# DOORLOCK.net
KiCad netlist of a schematic drawn in EAGLE
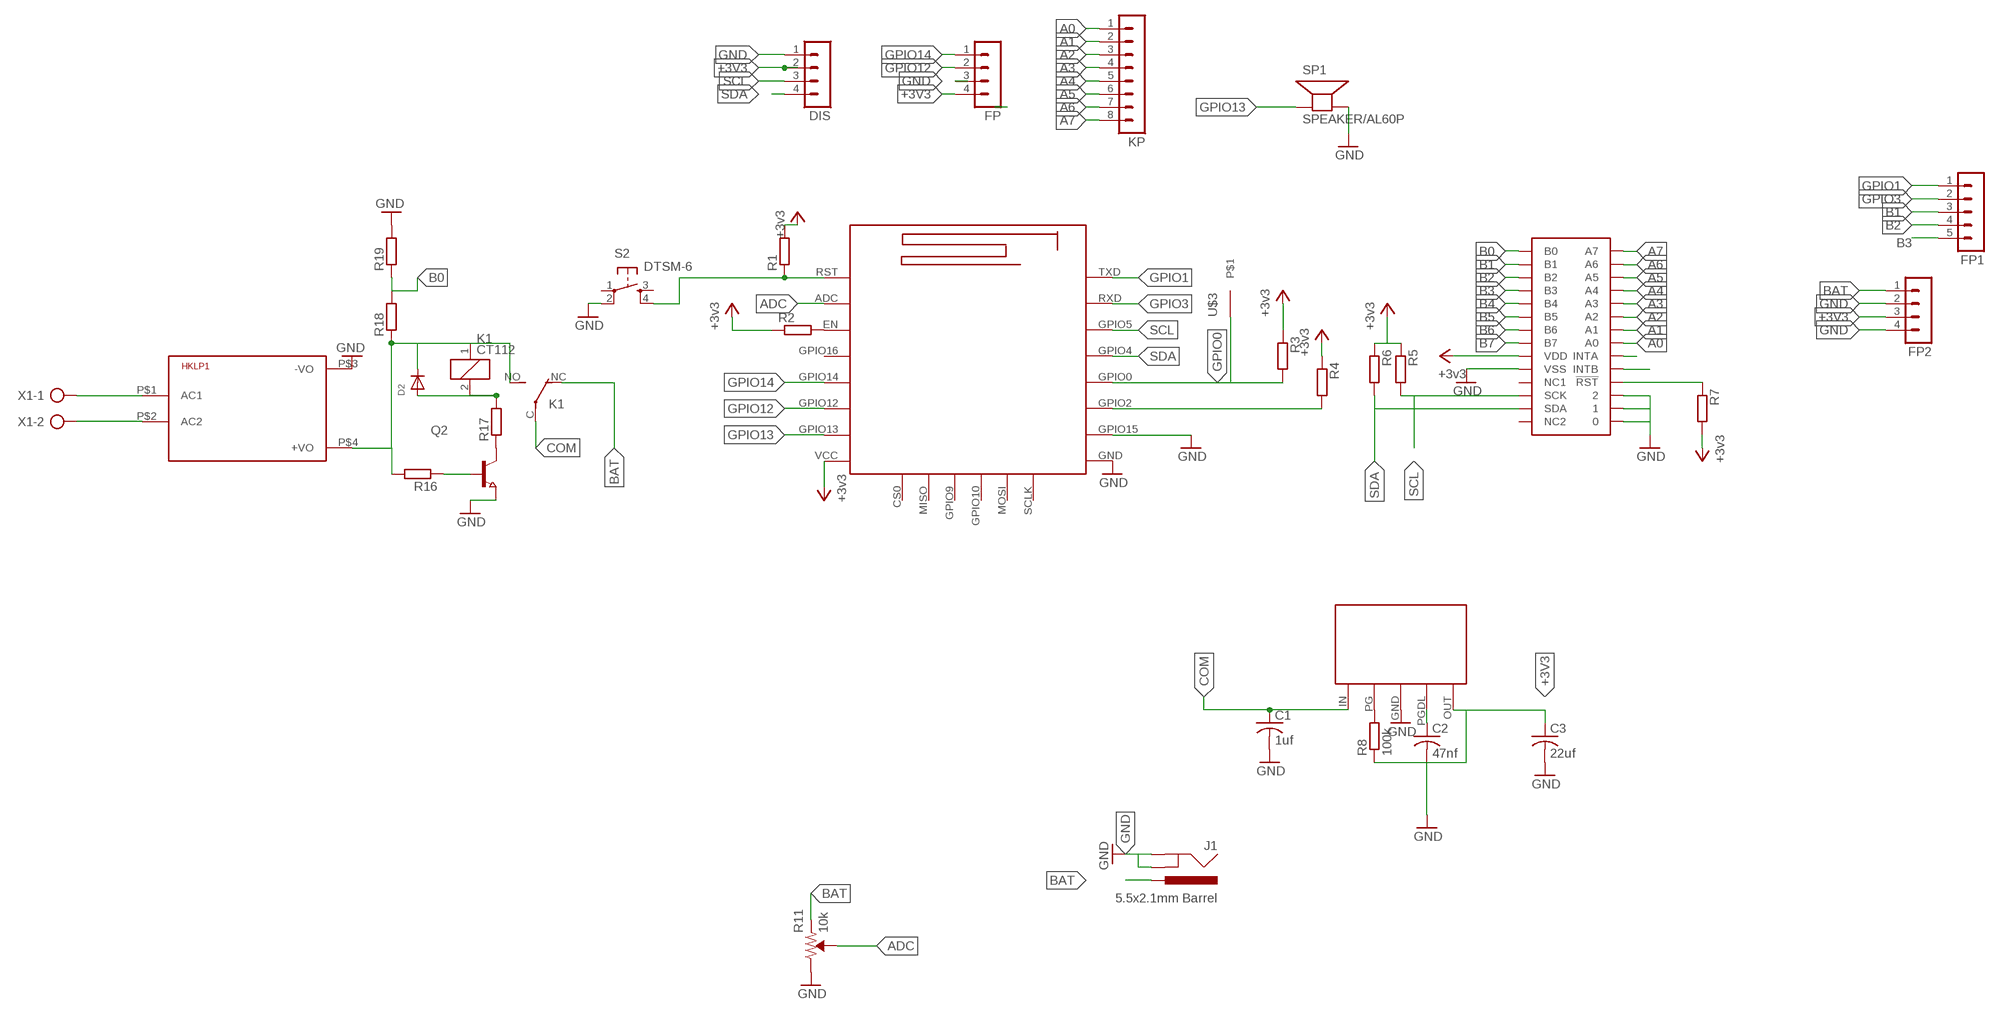
[diagram p0: schematic, sheet 1]

(export (version "E")
  (design (tool "Eeschema 10.0.6"))
  (components
    (comp (ref "C1")
      (value "1uf")
      (footprint "eagle-import:C1206")
      (libsource (lib "eagle-import") (part "C-USC1206"))
    )
    (comp (ref "C2")
      (value "47nf")
      (footprint "eagle-import:C1206")
      (libsource (lib "eagle-import") (part "C-USC1206"))
    )
    (comp (ref "C3")
      (value "22uf")
      (footprint "eagle-import:C1206")
      (libsource (lib "eagle-import") (part "C-USC1206"))
    )
    (comp (ref "D2")
      (value "DIODESOD-123")
      (footprint "eagle-import:SOD-123")
      (libsource (lib "eagle-import") (part "DIODESOD-123"))
    )
    (comp (ref "DIS")
      (value "MA04-1")
      (footprint "eagle-import:MA04-1")
      (libsource (lib "eagle-import") (part "MA04-1"))
    )
    (comp (ref "FP")
      (value "MA04-1")
      (footprint "eagle-import:MA04-1")
      (libsource (lib "eagle-import") (part "MA04-1"))
    )
    (comp (ref "FP1")
      (value "MA05-1")
      (footprint "eagle-import:MA05-1")
      (libsource (lib "eagle-import") (part "MA05-1"))
    )
    (comp (ref "FP2")
      (value "MA04-1")
      (footprint "eagle-import:MA04-1")
      (libsource (lib "eagle-import") (part "MA04-1"))
    )
    (comp (ref "HKLP1")
      (value "HKLPM01")
      (footprint "eagle-import:HKLPM01")
      (libsource (lib "eagle-import") (part "HKLPM01"))
    )
    (comp (ref "J1")
      (value "5.5x2.1mm Barrel")
      (footprint "eagle-import:POWER_JACK_SMD")
      (libsource (lib "eagle-import") (part "POWER_JACKSMD"))
    )
    (comp (ref "K1")
      (value "CT112")
      (footprint "eagle-import:CT-SLIM")
      (libsource (lib "eagle-import") (part "CT112"))
    )
    (comp (ref "KP")
      (value "MA08-1")
      (footprint "eagle-import:MA08-1")
      (libsource (lib "eagle-import") (part "MA08-1"))
    )
    (comp (ref "Q2")
      (value "NPN-TRANSISTOR_SOT89")
      (footprint "eagle-import:SOT89")
      (libsource (lib "eagle-import") (part "NPN-TRANSISTOR_SOT89"))
    )
    (comp (ref "R1")
      (value "R-EU_0204/2V")
      (footprint "eagle-import:0204V")
      (libsource (lib "eagle-import") (part "R-EU_0204/2V"))
    )
    (comp (ref "R2")
      (value "R-EU_0204/2V")
      (footprint "eagle-import:0204V")
      (libsource (lib "eagle-import") (part "R-EU_0204/2V"))
    )
    (comp (ref "R3")
      (value "R-EU_0204/2V")
      (footprint "eagle-import:0204V")
      (libsource (lib "eagle-import") (part "R-EU_0204/2V"))
    )
    (comp (ref "R4")
      (value "R-EU_0204/2V")
      (footprint "eagle-import:0204V")
      (libsource (lib "eagle-import") (part "R-EU_0204/2V"))
    )
    (comp (ref "R5")
      (value "R-EU_0204/2V")
      (footprint "eagle-import:0204V")
      (libsource (lib "eagle-import") (part "R-EU_0204/2V"))
    )
    (comp (ref "R6")
      (value "R-EU_0204/2V")
      (footprint "eagle-import:0204V")
      (libsource (lib "eagle-import") (part "R-EU_0204/2V"))
    )
    (comp (ref "R7")
      (value "R-EU_0204/2V")
      (footprint "eagle-import:0204V")
      (libsource (lib "eagle-import") (part "R-EU_0204/2V"))
    )
    (comp (ref "R8")
      (value "100k")
      (footprint "eagle-import:0204V")
      (libsource (lib "eagle-import") (part "R-EU_0204/2V"))
    )
    (comp (ref "R11")
      (value "10k")
      (footprint "eagle-import:TRIMPOT-SMD-TC33X")
      (libsource (lib "eagle-import") (part "TRIMPOT-SMD-3MM-OPEN-1/10W-25%"))
    )
    (comp (ref "R16")
      (value "R-EU_0204/2V")
      (footprint "eagle-import:0204V")
      (libsource (lib "eagle-import") (part "R-EU_0204/2V"))
    )
    (comp (ref "R17")
      (value "R-EU_0204/2V")
      (footprint "eagle-import:0204V")
      (libsource (lib "eagle-import") (part "R-EU_0204/2V"))
    )
    (comp (ref "R18")
      (value "R-EU_0204/2V")
      (footprint "eagle-import:0204V")
      (libsource (lib "eagle-import") (part "R-EU_0204/2V"))
    )
    (comp (ref "R19")
      (value "R-EU_0204/2V")
      (footprint "eagle-import:0204V")
      (libsource (lib "eagle-import") (part "R-EU_0204/2V"))
    )
    (comp (ref "S2")
      (value "DTSM-6")
      (footprint "eagle-import:DTSM-6")
      (libsource (lib "eagle-import") (part "DTSM-6"))
    )
    (comp (ref "SP1")
      (value "SPEAKER/AL60P")
      (footprint "eagle-import:AL60P")
      (libsource (lib "eagle-import") (part "SPEAKER/AL60P"))
    )
    (comp (ref "U$1")
      (value "ESP12E")
      (footprint "eagle-import:ESP-12E")
      (libsource (lib "eagle-import") (part "ESP12E"))
    )
    (comp (ref "U$2")
      (value "MCF23017")
      (footprint "eagle-import:MAX23017")
      (libsource (lib "eagle-import") (part "MCF23017"))
    )
    (comp (ref "U$3") (value "M1") (footprint "eagle-import:M1") (libsource (lib "eagle-import") (part "M1")))
    (comp (ref "U$4")
      (value "MP2014")
      (footprint "eagle-import:MP2014")
      (libsource (lib "eagle-import") (part "MP2014"))
    )
    (comp (ref "X1")
      (value "AK500/2-H")
      (footprint "eagle-import:AK500_2-H")
      (libsource (lib "eagle-import") (part "AK500/2-H"))
    )
  )
  (nets
    (net (code "1") (name "+3V3") (class "Default")
      (node (ref "C3") (pin "1") (pinfunction "1_1") (pintype "passive"))
      (node (ref "DIS") (pin "2") (pinfunction "2_2") (pintype "passive"))
      (node (ref "FP") (pin "4") (pinfunction "4_4") (pintype "passive"))
      (node (ref "FP2") (pin "3") (pinfunction "3_3") (pintype "passive"))
      (node (ref "R1") (pin "2") (pinfunction "2_2") (pintype "passive"))
      (node (ref "R2") (pin "1") (pinfunction "1_1") (pintype "passive"))
      (node (ref "R3") (pin "1") (pinfunction "1_1") (pintype "passive"))
      (node (ref "R4") (pin "1") (pinfunction "1_1") (pintype "passive"))
      (node (ref "R5") (pin "1") (pinfunction "1_1") (pintype "passive"))
      (node (ref "R6") (pin "1") (pinfunction "1_1") (pintype "passive"))
      (node (ref "R7") (pin "2") (pinfunction "2_2") (pintype "passive"))
      (node (ref "R8") (pin "1") (pinfunction "1_1") (pintype "passive"))
      (node (ref "U$1") (pin "VCC") (pinfunction "P$8_VCC") (pintype "bidirectional"))
      (node (ref "U$2") (pin "P$9") (pinfunction "VDD_P$9") (pintype "bidirectional"))
      (node (ref "U$4") (pin "OUT") (pinfunction "P$5_OUT") (pintype "bidirectional"))
    )
    (net (code "2") (name "A0") (class "Default")
      (node (ref "KP") (pin "1") (pinfunction "1_1") (pintype "passive"))
      (node (ref "U$2") (pin "P$21") (pinfunction "A0_P$21") (pintype "bidirectional"))
    )
    (net (code "3") (name "A1") (class "Default")
      (node (ref "KP") (pin "2") (pinfunction "2_2") (pintype "passive"))
      (node (ref "U$2") (pin "P$22") (pinfunction "A1_P$22") (pintype "bidirectional"))
    )
    (net (code "4") (name "A2") (class "Default")
      (node (ref "KP") (pin "3") (pinfunction "3_3") (pintype "passive"))
      (node (ref "U$2") (pin "P$23") (pinfunction "A2_P$23") (pintype "bidirectional"))
    )
    (net (code "5") (name "A3") (class "Default")
      (node (ref "KP") (pin "4") (pinfunction "4_4") (pintype "passive"))
      (node (ref "U$2") (pin "P$24") (pinfunction "A3_P$24") (pintype "bidirectional"))
    )
    (net (code "6") (name "A4") (class "Default")
      (node (ref "KP") (pin "5") (pinfunction "5_5") (pintype "passive"))
      (node (ref "U$2") (pin "P$25") (pinfunction "A4_P$25") (pintype "bidirectional"))
    )
    (net (code "7") (name "A5") (class "Default")
      (node (ref "KP") (pin "6") (pinfunction "6_6") (pintype "passive"))
      (node (ref "U$2") (pin "P$26") (pinfunction "A5_P$26") (pintype "bidirectional"))
    )
    (net (code "8") (name "A6") (class "Default")
      (node (ref "KP") (pin "7") (pinfunction "7_7") (pintype "passive"))
      (node (ref "U$2") (pin "P$27") (pinfunction "A6_P$27") (pintype "bidirectional"))
    )
    (net (code "9") (name "A7") (class "Default")
      (node (ref "KP") (pin "8") (pinfunction "8_8") (pintype "passive"))
      (node (ref "U$2") (pin "P$28") (pinfunction "A7_P$28") (pintype "bidirectional"))
    )
    (net (code "10") (name "ADC") (class "Default")
      (node (ref "R11") (pin "2") (pinfunction "WIPER_2") (pintype "passive"))
      (node (ref "U$1") (pin "ADC") (pinfunction "P$2_ADC") (pintype "bidirectional"))
    )
    (net (code "11") (name "B0") (class "Default")
      (node (ref "R18") (pin "2") (pinfunction "2_2") (pintype "passive"))
      (node (ref "R19") (pin "1") (pinfunction "1_1") (pintype "passive"))
      (node (ref "U$2") (pin "P$1") (pinfunction "B0_P$1") (pintype "bidirectional"))
    )
    (net (code "12") (name "B1") (class "Default")
      (node (ref "FP1") (pin "3") (pinfunction "3_3") (pintype "passive"))
      (node (ref "U$2") (pin "P$2") (pinfunction "B1_P$2") (pintype "bidirectional"))
    )
    (net (code "13") (name "B2") (class "Default")
      (node (ref "FP1") (pin "4") (pinfunction "4_4") (pintype "passive"))
      (node (ref "U$2") (pin "P$3") (pinfunction "B2_P$3") (pintype "bidirectional"))
    )
    (net (code "14") (name "B3") (class "Default")
      (node (ref "FP1") (pin "5") (pinfunction "5_5") (pintype "passive"))
      (node (ref "U$2") (pin "P$4") (pinfunction "B3_P$4") (pintype "bidirectional"))
    )
    (net (code "15") (name "B4") (class "Default")
      (node (ref "U$2") (pin "P$5") (pinfunction "B4_P$5") (pintype "bidirectional"))
    )
    (net (code "16") (name "B5") (class "Default")
      (node (ref "U$2") (pin "P$6") (pinfunction "B5_P$6") (pintype "bidirectional"))
    )
    (net (code "17") (name "B6") (class "Default")
      (node (ref "U$2") (pin "P$7") (pinfunction "B6_P$7") (pintype "bidirectional"))
    )
    (net (code "18") (name "B7") (class "Default")
      (node (ref "U$2") (pin "P$8") (pinfunction "B7_P$8") (pintype "bidirectional"))
    )
    (net (code "19") (name "BAT") (class "Default")
      (node (ref "FP2") (pin "1") (pinfunction "1_1") (pintype "passive"))
      (node (ref "J1") (pin "VIN0") (pinfunction "PWR_VIN0") (pintype "bidirectional"))
      (node (ref "K1") (pin "NC") (pinfunction "O_NC") (pintype "passive"))
      (node (ref "R11") (pin "3") (pinfunction "CCW_3") (pintype "passive"))
    )
    (net (code "20") (name "COM") (class "Default")
      (node (ref "C1") (pin "1") (pinfunction "1_1") (pintype "passive"))
      (node (ref "K1") (pin "C") (pinfunction "P_C") (pintype "passive"))
      (node (ref "U$4") (pin "IN") (pinfunction "P$1_IN") (pintype "bidirectional"))
    )
    (net (code "21") (name "GND") (class "Default")
      (node (ref "C1") (pin "2") (pinfunction "2_2") (pintype "passive"))
      (node (ref "C2") (pin "2") (pinfunction "2_2") (pintype "passive"))
      (node (ref "C3") (pin "2") (pinfunction "2_2") (pintype "passive"))
      (node (ref "DIS") (pin "1") (pinfunction "1_1") (pintype "passive"))
      (node (ref "FP") (pin "3") (pinfunction "3_3") (pintype "passive"))
      (node (ref "FP2") (pin "2") (pinfunction "2_2") (pintype "passive"))
      (node (ref "FP2") (pin "4") (pinfunction "4_4") (pintype "passive"))
      (node (ref "HKLP1") (pin "P$3") (pinfunction "-VO_P$3") (pintype "bidirectional"))
      (node (ref "J1") (pin "GND") (pinfunction "GNDBREAK_GND") (pintype "bidirectional"))
      (node (ref "J1") (pin "P$4") (pinfunction "GND_P$4") (pintype "bidirectional"))
      (node (ref "Q2") (pin "3") (pinfunction "E_3") (pintype "passive"))
      (node (ref "R11") (pin "1") (pinfunction "CW_1") (pintype "passive"))
      (node (ref "R19") (pin "2") (pinfunction "2_2") (pintype "passive"))
      (node (ref "S2") (pin "2") (pinfunction "2_2") (pintype "passive"))
      (node (ref "SP1") (pin "2") (pinfunction "-_2") (pintype "passive"))
      (node (ref "U$1") (pin "GND") (pinfunction "P$15_GND") (pintype "bidirectional"))
      (node (ref "U$1") (pin "GPIO15") (pinfunction "P$16_GPIO15") (pintype "bidirectional"))
      (node (ref "U$2") (pin "P$10") (pinfunction "VSS_P$10") (pintype "bidirectional"))
      (node (ref "U$2") (pin "P$15") (pinfunction "0_P$15") (pintype "bidirectional"))
      (node (ref "U$2") (pin "P$16") (pinfunction "1_P$16") (pintype "bidirectional"))
      (node (ref "U$2") (pin "P$17") (pinfunction "2_P$17") (pintype "bidirectional"))
      (node (ref "U$4") (pin "GND") (pinfunction "P$3_GND") (pintype "bidirectional"))
    )
    (net (code "22") (name "GPIO0") (class "Default")
      (node (ref "R3") (pin "2") (pinfunction "2_2") (pintype "passive"))
      (node (ref "U$1") (pin "GPIO0") (pinfunction "P$18_GPIO0") (pintype "bidirectional"))
      (node (ref "U$3") (pin "P$1") (pinfunction "P$1_P$1") (pintype "bidirectional"))
    )
    (net (code "23") (name "GPIO1") (class "Default")
      (node (ref "FP1") (pin "1") (pinfunction "1_1") (pintype "passive"))
      (node (ref "U$1") (pin "TXD") (pinfunction "P$22_TXD") (pintype "bidirectional"))
    )
    (net (code "24") (name "GPIO3") (class "Default")
      (node (ref "FP1") (pin "2") (pinfunction "2_2") (pintype "passive"))
      (node (ref "U$1") (pin "RXD") (pinfunction "P$21_RXD") (pintype "bidirectional"))
    )
    (net (code "25") (name "GPIO12") (class "Default")
      (node (ref "FP") (pin "2") (pinfunction "2_2") (pintype "passive"))
      (node (ref "U$1") (pin "GPIO12") (pinfunction "P$6_GPIO12") (pintype "bidirectional"))
    )
    (net (code "26") (name "GPIO13") (class "Default")
      (node (ref "SP1") (pin "1") (pinfunction "+_1") (pintype "passive"))
      (node (ref "U$1") (pin "GPIO13") (pinfunction "P$7_GPIO13") (pintype "bidirectional"))
    )
    (net (code "27") (name "GPIO14") (class "Default")
      (node (ref "FP") (pin "1") (pinfunction "1_1") (pintype "passive"))
      (node (ref "U$1") (pin "GPIO14") (pinfunction "P$5_GPIO14") (pintype "bidirectional"))
    )
    (net (code "28") (name "Net-(D2-PadA)") (class "Default")
      (node (ref "D2") (pin "A") (pinfunction "A_A") (pintype "passive"))
      (node (ref "K1") (pin "2") (pinfunction "2_2") (pintype "passive"))
      (node (ref "R17") (pin "2") (pinfunction "2_2") (pintype "passive"))
    )
    (net (code "29") (name "Net-(HKLP1-+VO)") (class "Default")
      (node (ref "D2") (pin "C") (pinfunction "C_C") (pintype "passive"))
      (node (ref "HKLP1") (pin "P$4") (pinfunction "+VO_P$4") (pintype "bidirectional"))
      (node (ref "K1") (pin "1") (pinfunction "1_1") (pintype "passive"))
      (node (ref "K1") (pin "NO") (pinfunction "S_NO") (pintype "passive"))
      (node (ref "R16") (pin "2") (pinfunction "2_2") (pintype "passive"))
      (node (ref "R18") (pin "1") (pinfunction "1_1") (pintype "passive"))
    )
    (net (code "30") (name "Net-(HKLP1-AC1)") (class "Default")
      (node (ref "HKLP1") (pin "P$1") (pinfunction "AC1_P$1") (pintype "bidirectional"))
      (node (ref "X1") (pin "1") (pinfunction "KL_1") (pintype "passive"))
    )
    (net (code "31") (name "Net-(HKLP1-AC2)") (class "Default")
      (node (ref "HKLP1") (pin "P$2") (pinfunction "AC2_P$2") (pintype "bidirectional"))
      (node (ref "X1") (pin "2") (pinfunction "KL_2") (pintype "passive"))
    )
    (net (code "32") (name "Net-(Q2-B)") (class "Default")
      (node (ref "Q2") (pin "1") (pinfunction "B_1") (pintype "passive"))
      (node (ref "R16") (pin "1") (pinfunction "1_1") (pintype "passive"))
    )
    (net (code "33") (name "Net-(Q2-C)") (class "Default")
      (node (ref "Q2") (pin "2") (pinfunction "C_2") (pintype "passive"))
      (node (ref "R17") (pin "1") (pinfunction "1_1") (pintype "passive"))
    )
    (net (code "34") (name "Net-(U$1-P$1)") (class "Default")
      (node (ref "R1") (pin "1") (pinfunction "1_1") (pintype "passive"))
      (node (ref "S2") (pin "4") (pinfunction "4_4") (pintype "passive"))
      (node (ref "U$1") (pin "RST") (pinfunction "P$1_RST") (pintype "bidirectional"))
    )
    (net (code "35") (name "Net-(U$1-P$3)") (class "Default")
      (node (ref "R2") (pin "2") (pinfunction "2_2") (pintype "passive"))
      (node (ref "U$1") (pin "EN") (pinfunction "P$3_EN") (pintype "bidirectional"))
    )
    (net (code "36") (name "Net-(U$1-P$17)") (class "Default")
      (node (ref "R4") (pin "2") (pinfunction "2_2") (pintype "passive"))
      (node (ref "U$1") (pin "GPIO2") (pinfunction "P$17_GPIO2") (pintype "bidirectional"))
    )
    (net (code "37") (name "Net-(U$2-~{RST})") (class "Default")
      (node (ref "R7") (pin "1") (pinfunction "1_1") (pintype "passive"))
      (node (ref "U$2") (pin "P$18") (pinfunction "~{RST}_P$18") (pintype "bidirectional"))
    )
    (net (code "38") (name "Net-(U$4-P$2)") (class "Default")
      (node (ref "R8") (pin "2") (pinfunction "2_2") (pintype "passive"))
      (node (ref "U$4") (pin "PG") (pinfunction "P$2_PG") (pintype "bidirectional"))
    )
    (net (code "39") (name "Net-(U$4-P$4)") (class "Default")
      (node (ref "C2") (pin "1") (pinfunction "1_1") (pintype "passive"))
      (node (ref "U$4") (pin "PGDL") (pinfunction "P$4_PGDL") (pintype "bidirectional"))
    )
    (net (code "40") (name "SCL") (class "Default")
      (node (ref "DIS") (pin "3") (pinfunction "3_3") (pintype "passive"))
      (node (ref "R5") (pin "2") (pinfunction "2_2") (pintype "passive"))
      (node (ref "U$1") (pin "GPIO5") (pinfunction "P$20_GPIO5") (pintype "bidirectional"))
      (node (ref "U$2") (pin "P$12") (pinfunction "SCK_P$12") (pintype "bidirectional"))
    )
    (net (code "41") (name "SDA") (class "Default")
      (node (ref "DIS") (pin "4") (pinfunction "4_4") (pintype "passive"))
      (node (ref "R6") (pin "2") (pinfunction "2_2") (pintype "passive"))
      (node (ref "U$1") (pin "GPIO4") (pinfunction "P$19_GPIO4") (pintype "bidirectional"))
      (node (ref "U$2") (pin "P$13") (pinfunction "SDA_P$13") (pintype "bidirectional"))
    )
    (net (code "42") (name "unconnected-(S2-Pad1)") (class "Default")
      (node (ref "S2") (pin "1") (pinfunction "1_1") (pintype "passive"))
    )
    (net (code "43") (name "unconnected-(S2-Pad3)") (class "Default")
      (node (ref "S2") (pin "3") (pinfunction "3_3") (pintype "passive"))
    )
    (net (code "44") (name "unconnected-(U$1-P$4-PadGPIO16)") (class "Default")
      (node (ref "U$1") (pin "GPIO16") (pinfunction "P$4_GPIO16") (pintype "bidirectional"))
    )
    (net (code "45") (name "unconnected-(U$1-P$9-PadCS0)") (class "Default")
      (node (ref "U$1") (pin "CS0") (pinfunction "P$9_CS0") (pintype "bidirectional"))
    )
    (net (code "46") (name "unconnected-(U$1-P$10-PadMISO)") (class "Default")
      (node (ref "U$1") (pin "MISO") (pinfunction "P$10_MISO") (pintype "bidirectional"))
    )
    (net (code "47") (name "unconnected-(U$1-P$11-PadGPIO9)") (class "Default")
      (node (ref "U$1") (pin "GPIO9") (pinfunction "P$11_GPIO9") (pintype "bidirectional"))
    )
    (net (code "48") (name "unconnected-(U$1-P$12-PadGPIO10)") (class "Default")
      (node (ref "U$1") (pin "GPIO10") (pinfunction "P$12_GPIO10") (pintype "bidirectional"))
    )
    (net (code "49") (name "unconnected-(U$1-P$13-PadMOSI)") (class "Default")
      (node (ref "U$1") (pin "MOSI") (pinfunction "P$13_MOSI") (pintype "bidirectional"))
    )
    (net (code "50") (name "unconnected-(U$1-P$14-PadSCLK)") (class "Default")
      (node (ref "U$1") (pin "SCLK") (pinfunction "P$14_SCLK") (pintype "bidirectional"))
    )
    (net (code "51") (name "unconnected-(U$2-INTA-PadP$20)") (class "Default")
      (node (ref "U$2") (pin "P$20") (pinfunction "INTA_P$20") (pintype "bidirectional"))
    )
    (net (code "52") (name "unconnected-(U$2-INTB-PadP$19)") (class "Default")
      (node (ref "U$2") (pin "P$19") (pinfunction "INTB_P$19") (pintype "bidirectional"))
    )
    (net (code "53") (name "unconnected-(U$2-NC1-PadP$11)") (class "Default")
      (node (ref "U$2") (pin "P$11") (pinfunction "NC1_P$11") (pintype "bidirectional"))
    )
    (net (code "54") (name "unconnected-(U$2-NC2-PadP$14)") (class "Default")
      (node (ref "U$2") (pin "P$14") (pinfunction "NC2_P$14") (pintype "bidirectional"))
    )
  )
)
